# P03_Battery_Circuit.net
KiCad netlist of a schematic drawn in Altium Designer
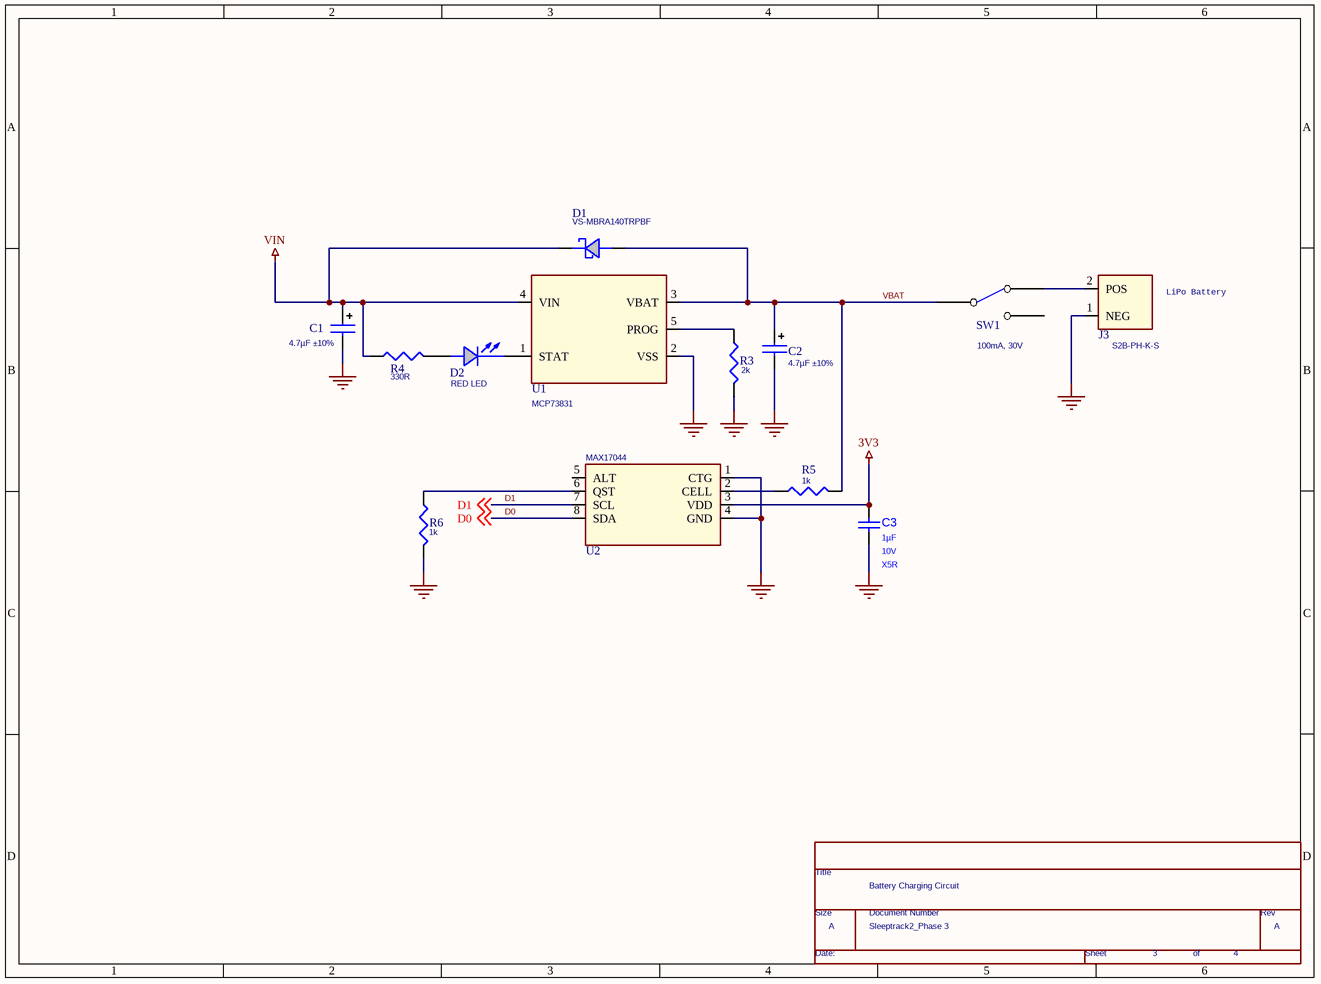
[diagram p0: P03_Battery Circuit.SchDoc]

(export (version "E")
  (design (tool "Eeschema 10.0.6"))
  (components
    (comp (ref "C1")
      (value "4.7µF ±10%")
      (footprint "CAPCP1206")
      (description "T491A475K006AT")
      (libsource (lib "SLEEPTRACK2_PHASE3_Library") (part "4.7µF ±10% Molded Tantalum Capacitors 6.3V 1206 (3216 Metric) 6 Ohm"))
    )
    (comp (ref "C2")
      (value "4.7µF ±10%")
      (footprint "CAPCP1206")
      (description "T491A475K006AT")
      (libsource (lib "SLEEPTRACK2_PHASE3_Library") (part "4.7µF ±10% Molded Tantalum Capacitors 6.3V 1206 (3216 Metric) 6 Ohm"))
    )
    (comp (ref "C3")
      (value "GRM155R61A105KE15D")
      (footprint "0402")
      (description "CAP, CERM, 1 µF, 10 V, +/- 10%, X5R, 0402")
      (fields
        (field (name "MANUFACTURER") "MuRata")
        (field (name "VALUEDISPLAYED") "1µF")
        (field (name "VALUE2") "10V")
        (field (name "TEMPCO") "X5R")
        (field (name "PUBLISHER") "Texas Instruments")
      )
      (libsource (lib "SLEEPTRACK2_PHASE3_Library") (part "GRM155R61A105KE15D"))
    )
    (comp (ref "D1")
      (value "VS-MBRA140TRPBF")
      (footprint "D0-214AC")
      (description "Diode Schottky 40V 1A Surface Mount SMA")
      (libsource (lib "SLEEPTRACK2_PHASE3_Library") (part "VS-MBRA140TRPBF"))
    )
    (comp (ref "D2")
      (value "RED LED")
      (footprint "LED0402N")
      (description "Red 631nm LED Indication - Discrete 2V 0402 (1005 Metric)")
      (libsource (lib "SLEEPTRACK2_PHASE3_Library") (part "VLMS1500-GS08"))
    )
    (comp (ref "J3")
      (value "S2B-PH-K-S")
      (footprint "S2B-PH-K-S")
      (description "2 Positions Header, Shrouded Connector 0.079\" (2.00mm) Through Hole, Right Angle Tin")
      (libsource (lib "SLEEPTRACK2_PHASE3_Library") (part "S2B-PH-K-S"))
    )
    (comp (ref "R3")
      (value "2k")
      (footprint "RESC402N")
      (description "RES SMD 2K OHM 1% 1/16W 0402")
      (libsource (lib "SLEEPTRACK2_PHASE3_Library") (part "RC0402FR-072KL"))
    )
    (comp (ref "R4")
      (value "330R")
      (footprint "RESC402N")
      (description "RES SMD 330R OHM 1% 1/16W 0402")
      (libsource (lib "SLEEPTRACK2_PHASE3_Library") (part "RC0402FR-07330RL"))
    )
    (comp (ref "R5")
      (value "1k")
      (footprint "RESC402N")
      (description "RES SMD 1K OHM 1% 1/16W 0402")
      (libsource (lib "SLEEPTRACK2_PHASE3_Library") (part "RC0402FR-071KL"))
    )
    (comp (ref "R6")
      (value "1k")
      (footprint "RESC402N")
      (description "RES SMD 1K OHM 1% 1/16W 0402")
      (libsource (lib "SLEEPTRACK2_PHASE3_Library") (part "RC0402FR-071KL"))
    )
    (comp (ref "SW1")
      (value "100mA, 30V")
      (footprint "SS12DH2")
      (description "Slide Switch SPDT Through Hole, Right Angle")
      (libsource (lib "SLEEPTRACK2_PHASE3_Library") (part "SS12SDH2"))
    )
    (comp (ref "U1")
      (value "MCP73831")
      (footprint "SOT95P270X145-5N")
      (description "Charger IC Lithium-Ion/Polymer SOT-23-5")
      (libsource (lib "SLEEPTRACK2_PHASE3_Library") (part "MCP73831"))
    )
    (comp (ref "U2")
      (value "MAX17044")
      (footprint "SON50P300X100_HS-9M")
      (description "Battery Battery Monitor IC Lithium-Ion/Polymer 8-TDFN (2x3)")
      (libsource (lib "SLEEPTRACK2_PHASE3_Library") (part "MAX17044"))
    )
  )
  (nets
    (net (code "1") (name "/VBAT") (class "Default")
      (node (ref "C2") (pin "1") (pinfunction "1_1") (pintype "passive"))
      (node (ref "D1") (pin "1") (pinfunction "ANODE_1") (pintype "passive"))
      (node (ref "R5") (pin "2") (pinfunction "2_2") (pintype "passive"))
      (node (ref "SW1") (pin "1") (pinfunction "COMMON_1") (pintype "passive"))
      (node (ref "U1") (pin "3") (pinfunction "VBAT_3") (pintype "passive"))
    )
    (net (code "2") (name "3V3") (class "Default")
      (node (ref "C3") (pin "1") (pinfunction "1_1") (pintype "passive"))
      (node (ref "U2") (pin "3") (pinfunction "VDD_3") (pintype "passive"))
    )
    (net (code "3") (name "D0") (class "Default")
      (node (ref "U2") (pin "8") (pinfunction "SDA_8") (pintype "passive"))
    )
    (net (code "4") (name "D1") (class "Default")
      (node (ref "U2") (pin "7") (pinfunction "SCL_7") (pintype "passive"))
    )
    (net (code "5") (name "GND") (class "Default")
      (node (ref "C1") (pin "2") (pinfunction "2_2") (pintype "passive"))
      (node (ref "C2") (pin "2") (pinfunction "2_2") (pintype "passive"))
      (node (ref "C3") (pin "2") (pinfunction "2_2") (pintype "passive"))
      (node (ref "J3") (pin "1") (pinfunction "NEG_1") (pintype "passive"))
      (node (ref "R3") (pin "2") (pinfunction "2_2") (pintype "passive"))
      (node (ref "R6") (pin "2") (pinfunction "2_2") (pintype "passive"))
      (node (ref "U1") (pin "2") (pinfunction "VSS_2") (pintype "passive"))
      (node (ref "U2") (pin "1") (pinfunction "CTG_1") (pintype "passive"))
      (node (ref "U2") (pin "4") (pinfunction "GND_4") (pintype "passive"))
    )
    (net (code "6") (name "Net-(D2-ANODE)") (class "Default")
      (node (ref "D2") (pin "2") (pinfunction "ANODE_2") (pintype "passive"))
      (node (ref "R4") (pin "2") (pinfunction "2_2") (pintype "passive"))
    )
    (net (code "7") (name "Net-(D2-CATHODE)") (class "Default")
      (node (ref "D2") (pin "1") (pinfunction "CATHODE_1") (pintype "passive"))
      (node (ref "U1") (pin "1") (pinfunction "STAT_1") (pintype "passive"))
    )
    (net (code "8") (name "Net-(J3-POS)") (class "Default")
      (node (ref "J3") (pin "2") (pinfunction "POS_2") (pintype "passive"))
      (node (ref "SW1") (pin "3") (pinfunction "NO_3") (pintype "passive"))
    )
    (net (code "9") (name "Net-(U1-PROG)") (class "Default")
      (node (ref "R3") (pin "1") (pinfunction "1_1") (pintype "passive"))
      (node (ref "U1") (pin "5") (pinfunction "PROG_5") (pintype "passive"))
    )
    (net (code "10") (name "Net-(U2-CELL)") (class "Default")
      (node (ref "R5") (pin "1") (pinfunction "1_1") (pintype "passive"))
      (node (ref "U2") (pin "2") (pinfunction "CELL_2") (pintype "passive"))
    )
    (net (code "11") (name "Net-(U2-QST)") (class "Default")
      (node (ref "R6") (pin "1") (pinfunction "1_1") (pintype "passive"))
      (node (ref "U2") (pin "6") (pinfunction "QST_6") (pintype "passive"))
    )
    (net (code "12") (name "VIN") (class "Default")
      (node (ref "C1") (pin "1") (pinfunction "1_1") (pintype "passive"))
      (node (ref "D1") (pin "2") (pinfunction "CATHODE_2") (pintype "passive"))
      (node (ref "R4") (pin "1") (pinfunction "1_1") (pintype "passive"))
      (node (ref "U1") (pin "4") (pinfunction "VIN_4") (pintype "passive"))
    )
    (net (code "13") (name "unconnected-(SW1-NC-Pad2)") (class "Default")
      (node (ref "SW1") (pin "2") (pinfunction "NC_2") (pintype "passive"))
    )
    (net (code "14") (name "unconnected-(U2-ALT-Pad5)") (class "Default")
      (node (ref "U2") (pin "5") (pinfunction "ALT_5") (pintype "passive"))
    )
  )
)
